# Sheet2.net
KiCad netlist of a schematic drawn in Altium Designer
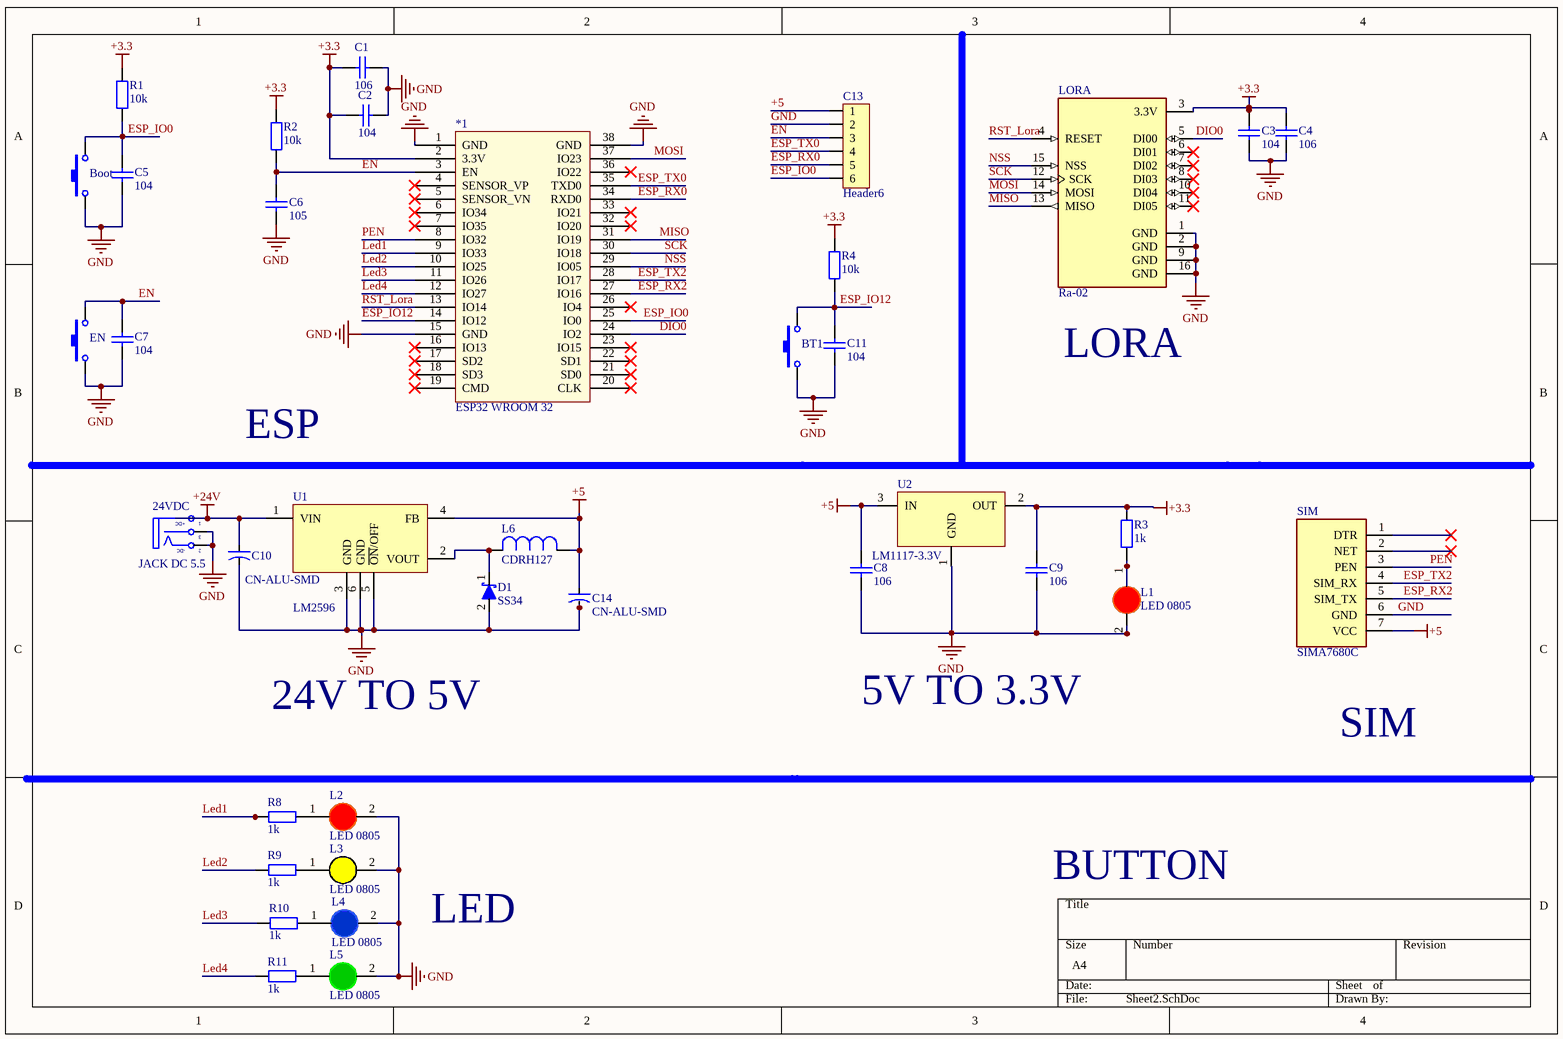
[diagram p0: Sheet2.SchDoc]

(export (version "E")
  (design (tool "Eeschema 10.0.6"))
  (components
    (comp (ref "*1")
      (value "ESP32 WROOM 32")
      (footprint "ESP32-WROOM-32D")
      (libsource (lib "Altium_Lib_by_KhueNguyenCreator") (part "ESP32 WROOM 32"))
    )
    (comp (ref "24VDC")
      (value "JACK DC 5.5")
      (footprint "JACK DC 5.5")
      (libsource (lib "Altium_Lib_by_KhueNguyenCreator") (part "JACK DC 5.5"))
    )
    (comp (ref "Boot")
      (value "Nut Nhan 2 Chan SMD 3x6x2.5")
      (footprint "Nut Nhan 2 Chan SMD 3x6x2.5")
      (libsource (lib "Altium_Lib_by_KhueNguyenCreator") (part "Nut Nhan 2 Chan SMD 3x6x2.5"))
    )
    (comp (ref "BT1")
      (value "Nut Nhan 2 Chan SMD 3x6x2.5")
      (footprint "Nut Nhan 2 Chan SMD 3x6x2.5")
      (libsource (lib "Altium_Lib_by_KhueNguyenCreator") (part "Nut Nhan 2 Chan SMD 3x6x2.5"))
    )
    (comp (ref "C1")
      (value "106")
      (footprint "tu 1206")
      (description "Dán")
      (libsource (lib "Altium_Lib_by_KhueNguyenCreator") (part "Tu 1206 106 16V 20%"))
    )
    (comp (ref "C2")
      (value "104")
      (footprint "tu 1206")
      (description "Dán")
      (libsource (lib "Altium_Lib_by_KhueNguyenCreator") (part "Tu 1206 104 50V 20%"))
    )
    (comp (ref "C3")
      (value "104")
      (footprint "tu 1206")
      (description "Dán")
      (libsource (lib "Altium_Lib_by_KhueNguyenCreator") (part "Tu 1206 104 50V 20%"))
    )
    (comp (ref "C4")
      (value "106")
      (footprint "tu 1206")
      (description "Dán")
      (libsource (lib "Altium_Lib_by_KhueNguyenCreator") (part "Tu 1206 106 16V 20%"))
    )
    (comp (ref "C5")
      (value "104")
      (footprint "tu 1206")
      (description "Dán")
      (libsource (lib "Altium_Lib_by_KhueNguyenCreator") (part "Tu 1206 104 50V 20%"))
    )
    (comp (ref "C6")
      (value "105")
      (footprint "tu 1206")
      (description "Dán")
      (libsource (lib "Altium_Lib_by_KhueNguyenCreator") (part "Tu 1206 105 50V 20%"))
    )
    (comp (ref "C7")
      (value "104")
      (footprint "tu 1206")
      (description "Dán")
      (libsource (lib "Altium_Lib_by_KhueNguyenCreator") (part "Tu 1206 104 50V 20%"))
    )
    (comp (ref "C8")
      (value "106")
      (footprint "tu 1206")
      (description "Dán")
      (libsource (lib "Altium_Lib_by_KhueNguyenCreator") (part "Tu 1206 106 16V 20%"))
    )
    (comp (ref "C9")
      (value "106")
      (footprint "tu 1206")
      (description "Dán")
      (libsource (lib "Altium_Lib_by_KhueNguyenCreator") (part "Tu 1206 106 16V 20%"))
    )
    (comp (ref "C10")
      (value "CN-ALU-SMD")
      (footprint "CAP-ALU-SMD-H")
      (description "Polarized Capacitor (Axial)")
      (fields (field (name "PUBLISHER") "Altium Limited"))
      (libsource (lib "TechMT.VN_Lib_Project v2") (part "CN-ALU-SMD"))
    )
    (comp (ref "C11")
      (value "104")
      (footprint "tu 1206")
      (description "Dán")
      (libsource (lib "Altium_Lib_by_KhueNguyenCreator") (part "Tu 1206 104 50V 20%"))
    )
    (comp (ref "C13")
      (value "Header6")
      (footprint "HDR6")
      (description "Header IDC, 6 x 1 Pin Vertical 2.54mm Pitch (Non-Boxed, Male)")
      (fields
        (field (name "MANUFACTURER") "Würth Elektronik eiSos GmbH")
        (field (name "PARTNO") "613002143121")
        (field (name "CREATED BY") "Karrer Zheng")
      )
      (libsource (lib "TechMT.VN_Lib_Project v2") (part "Header6"))
    )
    (comp (ref "C14")
      (value "CN-ALU-SMD")
      (footprint "CAP-ALU-SMD-D")
      (description "Polarized Capacitor (Axial)")
      (fields (field (name "PUBLISHER") "Altium Limited"))
      (libsource (lib "TechMT.VN_Lib_Project v2") (part "CN-ALU-SMD"))
    )
    (comp (ref "D1")
      (value "SS34")
      (footprint "DO-214AC")
      (description "Diode Schottky 40 V 5A Surface Mount DO-214AC (SMA)")
      (libsource (lib "My_lib") (part "SS54"))
    )
    (comp (ref "EN")
      (value "Nut Nhan 2 Chan SMD 3x6x2.5")
      (footprint "Nut Nhan 2 Chan SMD 3x6x2.5")
      (libsource (lib "Altium_Lib_by_KhueNguyenCreator") (part "Nut Nhan 2 Chan SMD 3x6x2.5"))
    )
    (comp (ref "L1")
      (value "LED 0805")
      (footprint "LED-1206-Red")
      (description "Dán")
      (libsource (lib "Altium_Lib_by_KhueNguyenCreator") (part "LED 1206 Do"))
    )
    (comp (ref "L2")
      (value "LED 0805")
      (footprint "LED-1206-Red")
      (description "Dán")
      (libsource (lib "Altium_Lib_by_KhueNguyenCreator") (part "LED 1206 Do"))
    )
    (comp (ref "L3")
      (value "LED 0805")
      (footprint "LED-1206-Yellow")
      (description "Dán")
      (libsource (lib "Altium_Lib_by_KhueNguyenCreator") (part "LED 1206 Vang"))
    )
    (comp (ref "L4")
      (value "LED 0805")
      (footprint "LED-1206-Blue")
      (description "Dán")
      (libsource (lib "Altium_Lib_by_KhueNguyenCreator") (part "LED 1206 Xanh Duong"))
    )
    (comp (ref "L5")
      (value "LED 0805")
      (footprint "LED-1206-Green")
      (description "Dán")
      (libsource (lib "Altium_Lib_by_KhueNguyenCreator") (part "LED 1206 Xanh La"))
    )
    (comp (ref "L6")
      (value "CDRH127")
      (footprint "33uH")
      (description "33uH - Inductor 4.2 A")
      (libsource (lib "My_lib") (part "CDRH127"))
    )
    (comp (ref "LORA")
      (value "Ra-02")
      (footprint "Sx1278")
      (description "Lora sx1278")
      (libsource (lib "My_lib") (part "Ra-02"))
    )
    (comp (ref "R1")
      (value "10k")
      (footprint "tro smd 1206")
      (description "Dán")
      (libsource (lib "Altium_Lib_by_KhueNguyenCreator") (part "Tro 1206 5% 1k"))
    )
    (comp (ref "R2")
      (value "10k")
      (footprint "tro smd 1206")
      (description "Dán")
      (libsource (lib "Altium_Lib_by_KhueNguyenCreator") (part "Tro 1206 1% 10k"))
    )
    (comp (ref "R3")
      (value "1k")
      (footprint "Tro smd 1206")
      (description "Dán")
      (libsource (lib "Altium_Lib_by_KhueNguyenCreator") (part "Tro 1206 5% 390R"))
    )
    (comp (ref "R4")
      (value "10k")
      (footprint "tro smd 1206")
      (description "Dán")
      (libsource (lib "Altium_Lib_by_KhueNguyenCreator") (part "Tro 1206 5% 1k"))
    )
    (comp (ref "R8")
      (value "1k")
      (footprint "Tro smd 1206")
      (description "Dán")
      (libsource (lib "Altium_Lib_by_KhueNguyenCreator") (part "Tro 1206 5% 390R"))
    )
    (comp (ref "R9")
      (value "1k")
      (footprint "Tro smd 1206")
      (description "Dán")
      (libsource (lib "Altium_Lib_by_KhueNguyenCreator") (part "Tro 1206 5% 390R"))
    )
    (comp (ref "R10")
      (value "1k")
      (footprint "Tro smd 1206")
      (description "Dán")
      (libsource (lib "Altium_Lib_by_KhueNguyenCreator") (part "Tro 1206 5% 390R"))
    )
    (comp (ref "R11")
      (value "1k")
      (footprint "Tro smd 1206")
      (description "Dán")
      (libsource (lib "Altium_Lib_by_KhueNguyenCreator") (part "Tro 1206 5% 390R"))
    )
    (comp (ref "SIM")
      (value "SIMA7680C")
      (footprint "SIMA7680C")
      (libsource (lib "My_lib") (part "SIMA7680C"))
    )
    (comp (ref "U1")
      (value "LM2596")
      (footprint "MinhTien_PcbLib:TO263-5")
      (description "1A Regulator")
      (libsource (lib "MinhTien_SCHLib") (part "LM2596"))
    )
    (comp (ref "U2")
      (value "LM1117-3.3V")
      (footprint "SOT223")
      (description "800mA Low-Dropout Linear Regulator")
      (fields (field (name "CREATOR") "Nguyen Ba Bien"))
      (libsource (lib "TechMT.VN_Lib_Project v2") (part "LM1117"))
    )
  )
  (nets
    (net (code "1") (name "+3.3") (class "Default")
      (node (ref "*1") (pin "2") (pinfunction "3.3V_2") (pintype "passive"))
      (node (ref "C1") (pin "2") (pinfunction "2_2") (pintype "passive"))
      (node (ref "C2") (pin "2") (pinfunction "2_2") (pintype "passive"))
      (node (ref "C3") (pin "1") (pinfunction "1_1") (pintype "passive"))
      (node (ref "C4") (pin "1") (pinfunction "1_1") (pintype "passive"))
      (node (ref "C9") (pin "1") (pinfunction "1_1") (pintype "passive"))
      (node (ref "LORA") (pin "3") (pinfunction "3.3V_3") (pintype "power_in"))
      (node (ref "R1") (pin "2") (pinfunction "2_2") (pintype "passive"))
      (node (ref "R2") (pin "2") (pinfunction "2_2") (pintype "passive"))
      (node (ref "R3") (pin "1") (pinfunction "1_1") (pintype "passive"))
      (node (ref "R4") (pin "2") (pinfunction "2_2") (pintype "passive"))
      (node (ref "U2") (pin "2") (pinfunction "OUT_2") (pintype "passive"))
    )
    (net (code "2") (name "+5") (class "Default")
      (node (ref "C13") (pin "1") (pinfunction "1_1") (pintype "passive"))
      (node (ref "C14") (pin "1") (pinfunction "1_1") (pintype "passive"))
      (node (ref "C8") (pin "1") (pinfunction "1_1") (pintype "passive"))
      (node (ref "L6") (pin "1") (pinfunction "1_1") (pintype "passive"))
      (node (ref "SIM") (pin "7") (pinfunction "VCC_7") (pintype "power_in"))
      (node (ref "U1") (pin "4") (pinfunction "FB_4") (pintype "passive"))
      (node (ref "U2") (pin "3") (pinfunction "IN_3") (pintype "passive"))
    )
    (net (code "3") (name "+24V") (class "Default")
      (node (ref "24VDC") (pin "1") (pinfunction "T_1") (pintype "passive"))
      (node (ref "C10") (pin "1") (pinfunction "1_1") (pintype "passive"))
      (node (ref "U1") (pin "1") (pinfunction "VIN_1") (pintype "passive"))
    )
    (net (code "5") (name "/DIO0") (class "Default")
      (node (ref "*1") (pin "24") (pinfunction "IO2_24") (pintype "passive"))
      (node (ref "LORA") (pin "5") (pinfunction "DI00_5") (pintype "bidirectional"))
    )
    (net (code "6") (name "/EN") (class "Default")
      (node (ref "*1") (pin "3") (pinfunction "EN_3") (pintype "passive"))
      (node (ref "C13") (pin "3") (pinfunction "3_3") (pintype "passive"))
      (node (ref "C6") (pin "1") (pinfunction "1_1") (pintype "passive"))
      (node (ref "C7") (pin "1") (pinfunction "1_1") (pintype "passive"))
      (node (ref "EN") (pin "2") (pinfunction "2_2") (pintype "passive"))
      (node (ref "R2") (pin "1") (pinfunction "1_1") (pintype "passive"))
    )
    (net (code "7") (name "/ESP_IO0") (class "Default")
      (node (ref "*1") (pin "25") (pinfunction "IO0_25") (pintype "passive"))
      (node (ref "Boot") (pin "2") (pinfunction "2_2") (pintype "passive"))
      (node (ref "C13") (pin "6") (pinfunction "6_6") (pintype "passive"))
      (node (ref "C5") (pin "1") (pinfunction "1_1") (pintype "passive"))
      (node (ref "R1") (pin "1") (pinfunction "1_1") (pintype "passive"))
    )
    (net (code "8") (name "/ESP_IO12") (class "Default")
      (node (ref "*1") (pin "14") (pinfunction "IO12_14") (pintype "passive"))
      (node (ref "BT1") (pin "2") (pinfunction "2_2") (pintype "passive"))
      (node (ref "C11") (pin "1") (pinfunction "1_1") (pintype "passive"))
      (node (ref "R4") (pin "1") (pinfunction "1_1") (pintype "passive"))
    )
    (net (code "9") (name "/ESP_RX0") (class "Default")
      (node (ref "*1") (pin "34") (pinfunction "RXD0_34") (pintype "passive"))
      (node (ref "C13") (pin "5") (pinfunction "5_5") (pintype "passive"))
    )
    (net (code "10") (name "/ESP_RX2") (class "Default")
      (node (ref "*1") (pin "27") (pinfunction "IO16_27") (pintype "passive"))
      (node (ref "SIM") (pin "5") (pinfunction "SIM_TX_5") (pintype "power_in"))
    )
    (net (code "11") (name "/ESP_TX0") (class "Default")
      (node (ref "*1") (pin "35") (pinfunction "TXD0_35") (pintype "passive"))
      (node (ref "C13") (pin "4") (pinfunction "4_4") (pintype "passive"))
    )
    (net (code "12") (name "/ESP_TX2") (class "Default")
      (node (ref "*1") (pin "28") (pinfunction "IO17_28") (pintype "passive"))
      (node (ref "SIM") (pin "4") (pinfunction "SIM_RX_4") (pintype "power_in"))
    )
    (net (code "13") (name "/Led1") (class "Default")
      (node (ref "*1") (pin "9") (pinfunction "IO33_9") (pintype "passive"))
      (node (ref "R8") (pin "2") (pinfunction "2_2") (pintype "passive"))
    )
    (net (code "14") (name "/Led2") (class "Default")
      (node (ref "*1") (pin "10") (pinfunction "IO25_10") (pintype "passive"))
      (node (ref "R9") (pin "2") (pinfunction "2_2") (pintype "passive"))
    )
    (net (code "15") (name "/Led3") (class "Default")
      (node (ref "*1") (pin "11") (pinfunction "IO26_11") (pintype "passive"))
      (node (ref "R10") (pin "2") (pinfunction "2_2") (pintype "passive"))
    )
    (net (code "16") (name "/Led4") (class "Default")
      (node (ref "*1") (pin "12") (pinfunction "IO27_12") (pintype "passive"))
      (node (ref "R11") (pin "2") (pinfunction "2_2") (pintype "passive"))
    )
    (net (code "17") (name "/MISO") (class "Default")
      (node (ref "*1") (pin "31") (pinfunction "IO19_31") (pintype "passive"))
      (node (ref "LORA") (pin "13") (pinfunction "MISO_13") (pintype "output"))
    )
    (net (code "18") (name "/MOSI") (class "Default")
      (node (ref "*1") (pin "37") (pinfunction "IO23_37") (pintype "passive"))
      (node (ref "LORA") (pin "14") (pinfunction "MOSI_14") (pintype "input"))
    )
    (net (code "19") (name "/NSS") (class "Default")
      (node (ref "*1") (pin "29") (pinfunction "IO05_29") (pintype "passive"))
      (node (ref "LORA") (pin "15") (pinfunction "NSS_15") (pintype "input"))
    )
    (net (code "20") (name "/PEN") (class "Default")
      (node (ref "*1") (pin "8") (pinfunction "IO32_8") (pintype "passive"))
      (node (ref "SIM") (pin "3") (pinfunction "PEN_3") (pintype "power_in"))
    )
    (net (code "21") (name "/RST_Lora") (class "Default")
      (node (ref "*1") (pin "13") (pinfunction "IO14_13") (pintype "passive"))
      (node (ref "LORA") (pin "4") (pinfunction "RESET_4") (pintype "input"))
    )
    (net (code "22") (name "/SCK") (class "Default")
      (node (ref "*1") (pin "30") (pinfunction "IO18_30") (pintype "passive"))
      (node (ref "LORA") (pin "12") (pinfunction "SCK_12") (pintype "input"))
    )
    (net (code "23") (name "GND") (class "Default")
      (node (ref "*1") (pin "1") (pinfunction "GND_1") (pintype "passive"))
      (node (ref "*1") (pin "15") (pinfunction "GND_15") (pintype "passive"))
      (node (ref "*1") (pin "38") (pinfunction "GND_38") (pintype "passive"))
      (node (ref "24VDC") (pin "2") (pinfunction "TN_2") (pintype "passive"))
      (node (ref "24VDC") (pin "3") (pinfunction "S_3") (pintype "power_in"))
      (node (ref "BT1") (pin "1") (pinfunction "1_1") (pintype "passive"))
      (node (ref "Boot") (pin "1") (pinfunction "1_1") (pintype "passive"))
      (node (ref "C1") (pin "1") (pinfunction "1_1") (pintype "passive"))
      (node (ref "C10") (pin "2") (pinfunction "2_2") (pintype "passive"))
      (node (ref "C11") (pin "2") (pinfunction "2_2") (pintype "passive"))
      (node (ref "C13") (pin "2") (pinfunction "2_2") (pintype "passive"))
      (node (ref "C14") (pin "2") (pinfunction "2_2") (pintype "passive"))
      (node (ref "C2") (pin "1") (pinfunction "1_1") (pintype "passive"))
      (node (ref "C3") (pin "2") (pinfunction "2_2") (pintype "passive"))
      (node (ref "C4") (pin "2") (pinfunction "2_2") (pintype "passive"))
      (node (ref "C5") (pin "2") (pinfunction "2_2") (pintype "passive"))
      (node (ref "C6") (pin "2") (pinfunction "2_2") (pintype "passive"))
      (node (ref "C7") (pin "2") (pinfunction "2_2") (pintype "passive"))
      (node (ref "C8") (pin "2") (pinfunction "2_2") (pintype "passive"))
      (node (ref "C9") (pin "2") (pinfunction "2_2") (pintype "passive"))
      (node (ref "D1") (pin "2") (pinfunction "A_2") (pintype "bidirectional"))
      (node (ref "EN") (pin "1") (pinfunction "1_1") (pintype "passive"))
      (node (ref "L1") (pin "2") (pinfunction "K_2") (pintype "passive"))
      (node (ref "L2") (pin "2") (pinfunction "K_2") (pintype "passive"))
      (node (ref "L3") (pin "2") (pinfunction "K_2") (pintype "passive"))
      (node (ref "L4") (pin "2") (pinfunction "K_2") (pintype "passive"))
      (node (ref "L5") (pin "2") (pinfunction "K_2") (pintype "passive"))
      (node (ref "LORA") (pin "1") (pinfunction "GND_1") (pintype "power_in"))
      (node (ref "LORA") (pin "16") (pinfunction "GND_16") (pintype "power_in"))
      (node (ref "LORA") (pin "2") (pinfunction "GND_2") (pintype "power_in"))
      (node (ref "LORA") (pin "9") (pinfunction "GND_9") (pintype "power_in"))
      (node (ref "SIM") (pin "6") (pinfunction "GND_6") (pintype "power_in"))
      (node (ref "U1") (pin "3") (pinfunction "GND_3") (pintype "passive"))
      (node (ref "U1") (pin "5") (pinfunction "~{ON}/OFF_5") (pintype "passive"))
      (node (ref "U1") (pin "6") (pinfunction "GND_6") (pintype "passive"))
      (node (ref "U2") (pin "1") (pinfunction "GND_1") (pintype "passive"))
    )
    (net (code "24") (name "Net-(D1-K)") (class "Default")
      (node (ref "D1") (pin "1") (pinfunction "K_1") (pintype "bidirectional"))
      (node (ref "L6") (pin "2") (pinfunction "2_2") (pintype "passive"))
      (node (ref "U1") (pin "2") (pinfunction "VOUT_2") (pintype "passive"))
    )
    (net (code "25") (name "Net-(L1-A)") (class "Default")
      (node (ref "L1") (pin "1") (pinfunction "A_1") (pintype "passive"))
      (node (ref "R3") (pin "2") (pinfunction "2_2") (pintype "passive"))
    )
    (net (code "26") (name "Net-(L2-A)") (class "Default")
      (node (ref "L2") (pin "1") (pinfunction "A_1") (pintype "passive"))
      (node (ref "R8") (pin "1") (pinfunction "1_1") (pintype "passive"))
    )
    (net (code "27") (name "Net-(L3-A)") (class "Default")
      (node (ref "L3") (pin "1") (pinfunction "A_1") (pintype "passive"))
      (node (ref "R9") (pin "1") (pinfunction "1_1") (pintype "passive"))
    )
    (net (code "28") (name "Net-(L4-A)") (class "Default")
      (node (ref "L4") (pin "1") (pinfunction "A_1") (pintype "passive"))
      (node (ref "R10") (pin "1") (pinfunction "1_1") (pintype "passive"))
    )
    (net (code "29") (name "Net-(L5-A)") (class "Default")
      (node (ref "L5") (pin "1") (pinfunction "A_1") (pintype "passive"))
      (node (ref "R11") (pin "1") (pinfunction "1_1") (pintype "passive"))
    )
    (net (code "30") (name "unconnected-(*1-CLK-Pad20)") (class "Default")
      (node (ref "*1") (pin "20") (pinfunction "CLK_20") (pintype "passive+no_connect"))
    )
    (net (code "31") (name "unconnected-(*1-CMD-Pad19)") (class "Default")
      (node (ref "*1") (pin "19") (pinfunction "CMD_19") (pintype "passive+no_connect"))
    )
    (net (code "32") (name "unconnected-(*1-IO4-Pad26)") (class "Default")
      (node (ref "*1") (pin "26") (pinfunction "IO4_26") (pintype "passive+no_connect"))
    )
    (net (code "33") (name "unconnected-(*1-IO13-Pad16)") (class "Default")
      (node (ref "*1") (pin "16") (pinfunction "IO13_16") (pintype "passive+no_connect"))
    )
    (net (code "34") (name "unconnected-(*1-IO15-Pad23)") (class "Default")
      (node (ref "*1") (pin "23") (pinfunction "IO15_23") (pintype "passive+no_connect"))
    )
    (net (code "35") (name "unconnected-(*1-IO20-Pad32)") (class "Default")
      (node (ref "*1") (pin "32") (pinfunction "IO20_32") (pintype "passive+no_connect"))
    )
    (net (code "36") (name "unconnected-(*1-IO21-Pad33)") (class "Default")
      (node (ref "*1") (pin "33") (pinfunction "IO21_33") (pintype "passive+no_connect"))
    )
    (net (code "37") (name "unconnected-(*1-IO22-Pad36)") (class "Default")
      (node (ref "*1") (pin "36") (pinfunction "IO22_36") (pintype "passive+no_connect"))
    )
    (net (code "38") (name "unconnected-(*1-IO34-Pad6)") (class "Default")
      (node (ref "*1") (pin "6") (pinfunction "IO34_6") (pintype "passive+no_connect"))
    )
    (net (code "39") (name "unconnected-(*1-IO35-Pad7)") (class "Default")
      (node (ref "*1") (pin "7") (pinfunction "IO35_7") (pintype "passive+no_connect"))
    )
    (net (code "40") (name "unconnected-(*1-SD0-Pad21)") (class "Default")
      (node (ref "*1") (pin "21") (pinfunction "SD0_21") (pintype "passive+no_connect"))
    )
    (net (code "41") (name "unconnected-(*1-SD1-Pad22)") (class "Default")
      (node (ref "*1") (pin "22") (pinfunction "SD1_22") (pintype "passive+no_connect"))
    )
    (net (code "42") (name "unconnected-(*1-SD2-Pad17)") (class "Default")
      (node (ref "*1") (pin "17") (pinfunction "SD2_17") (pintype "passive+no_connect"))
    )
    (net (code "43") (name "unconnected-(*1-SD3-Pad18)") (class "Default")
      (node (ref "*1") (pin "18") (pinfunction "SD3_18") (pintype "passive+no_connect"))
    )
    (net (code "44") (name "unconnected-(*1-SENSOR_VN-Pad5)") (class "Default")
      (node (ref "*1") (pin "5") (pinfunction "SENSOR_VN_5") (pintype "passive+no_connect"))
    )
    (net (code "45") (name "unconnected-(*1-SENSOR_VP-Pad4)") (class "Default")
      (node (ref "*1") (pin "4") (pinfunction "SENSOR_VP_4") (pintype "passive+no_connect"))
    )
    (net (code "46") (name "unconnected-(LORA-DI01-Pad6)") (class "Default")
      (node (ref "LORA") (pin "6") (pinfunction "DI01_6") (pintype "bidirectional+no_connect"))
    )
    (net (code "47") (name "unconnected-(LORA-DI02-Pad7)") (class "Default")
      (node (ref "LORA") (pin "7") (pinfunction "DI02_7") (pintype "bidirectional+no_connect"))
    )
    (net (code "48") (name "unconnected-(LORA-DI03-Pad8)") (class "Default")
      (node (ref "LORA") (pin "8") (pinfunction "DI03_8") (pintype "bidirectional+no_connect"))
    )
    (net (code "49") (name "unconnected-(LORA-DI04-Pad10)") (class "Default")
      (node (ref "LORA") (pin "10") (pinfunction "DI04_10") (pintype "bidirectional+no_connect"))
    )
    (net (code "50") (name "unconnected-(LORA-DI05-Pad11)") (class "Default")
      (node (ref "LORA") (pin "11") (pinfunction "DI05_11") (pintype "bidirectional+no_connect"))
    )
    (net (code "51") (name "unconnected-(SIM-DTR-Pad1)") (class "Default")
      (node (ref "SIM") (pin "1") (pinfunction "DTR_1") (pintype "passive+no_connect"))
    )
    (net (code "52") (name "unconnected-(SIM-NET-Pad2)") (class "Default")
      (node (ref "SIM") (pin "2") (pinfunction "NET_2") (pintype "passive+no_connect"))
    )
  )
)
